# main.net
KiCad netlist of a schematic drawn in EAGLE
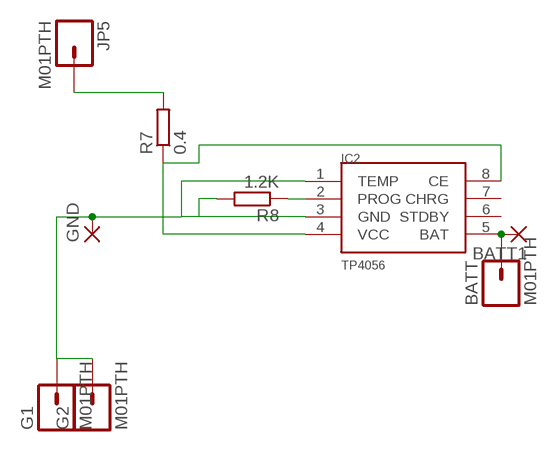
[diagram p0: schematic, sheet 1]

(export (version "E")
  (design (tool "Eeschema 10.0.6"))
  (components
    (comp (ref "BATT")
      (value "M01PTH")
      (footprint "eagle-import:1X01")
      (libsource (lib "eagle-import") (part "M01PTH"))
    )
    (comp (ref "BATT1")
      (value "SMD2")
      (footprint "eagle-import:SMD1,27-2,54")
      (libsource (lib "eagle-import") (part "SMD2"))
    )
    (comp (ref "G1")
      (value "M01PTH")
      (footprint "eagle-import:1X01")
      (libsource (lib "eagle-import") (part "M01PTH"))
    )
    (comp (ref "G2")
      (value "M01PTH")
      (footprint "eagle-import:1X01")
      (libsource (lib "eagle-import") (part "M01PTH"))
    )
    (comp (ref "GND")
      (value "SMD2")
      (footprint "eagle-import:SMD1,27-2,54")
      (libsource (lib "eagle-import") (part "SMD2"))
    )
    (comp (ref "IC2")
      (value "TP4056")
      (footprint "eagle-import:SOP-8")
      (libsource (lib "eagle-import") (part "TP4056"))
    )
    (comp (ref "JP5")
      (value "M01PTH")
      (footprint "eagle-import:1X01")
      (libsource (lib "eagle-import") (part "M01PTH"))
    )
    (comp (ref "R7")
      (value "0.4")
      (footprint "eagle-import:M0805")
      (libsource (lib "eagle-import") (part "R-EU_M0805"))
    )
    (comp (ref "R8")
      (value "1.2K")
      (footprint "eagle-import:R0603")
      (libsource (lib "eagle-import") (part "R-EU_R0603"))
    )
  )
  (nets
    (net (code "1") (name "Net-(BATT1-P)") (class "Default")
      (node (ref "BATT") (pin "1") (pinfunction "1_1") (pintype "passive"))
      (node (ref "BATT1") (pin "1") (pinfunction "P_1") (pintype "passive"))
      (node (ref "IC2") (pin "5") (pinfunction "BAT_5") (pintype "bidirectional"))
    )
    (net (code "2") (name "Net-(GND-P)") (class "Default")
      (node (ref "G1") (pin "1") (pinfunction "1_1") (pintype "passive"))
      (node (ref "G2") (pin "1") (pinfunction "1_1") (pintype "passive"))
      (node (ref "GND") (pin "1") (pinfunction "P_1") (pintype "passive"))
      (node (ref "IC2") (pin "1") (pinfunction "TEMP_1") (pintype "bidirectional"))
      (node (ref "IC2") (pin "3") (pinfunction "GND_3") (pintype "bidirectional"))
      (node (ref "R8") (pin "2") (pinfunction "2_2") (pintype "passive"))
    )
    (net (code "3") (name "Net-(IC2-CE)") (class "Default")
      (node (ref "IC2") (pin "4") (pinfunction "VCC_4") (pintype "bidirectional"))
      (node (ref "IC2") (pin "8") (pinfunction "CE_8") (pintype "bidirectional"))
      (node (ref "R7") (pin "1") (pinfunction "1_1") (pintype "passive"))
    )
    (net (code "4") (name "Net-(IC2-PROG)") (class "Default")
      (node (ref "IC2") (pin "2") (pinfunction "PROG_2") (pintype "bidirectional"))
      (node (ref "R8") (pin "1") (pinfunction "1_1") (pintype "passive"))
    )
    (net (code "5") (name "Net-(JP5-Pad1)") (class "Default")
      (node (ref "JP5") (pin "1") (pinfunction "1_1") (pintype "passive"))
      (node (ref "R7") (pin "2") (pinfunction "2_2") (pintype "passive"))
    )
    (net (code "6") (name "unconnected-(IC2-CHRG-Pad7)") (class "Default")
      (node (ref "IC2") (pin "7") (pinfunction "CHRG_7") (pintype "bidirectional"))
    )
    (net (code "7") (name "unconnected-(IC2-STDBY-Pad6)") (class "Default")
      (node (ref "IC2") (pin "6") (pinfunction "STDBY_6") (pintype "bidirectional"))
    )
  )
)
